# usb-can.net
KiCad netlist of a schematic drawn in EAGLE
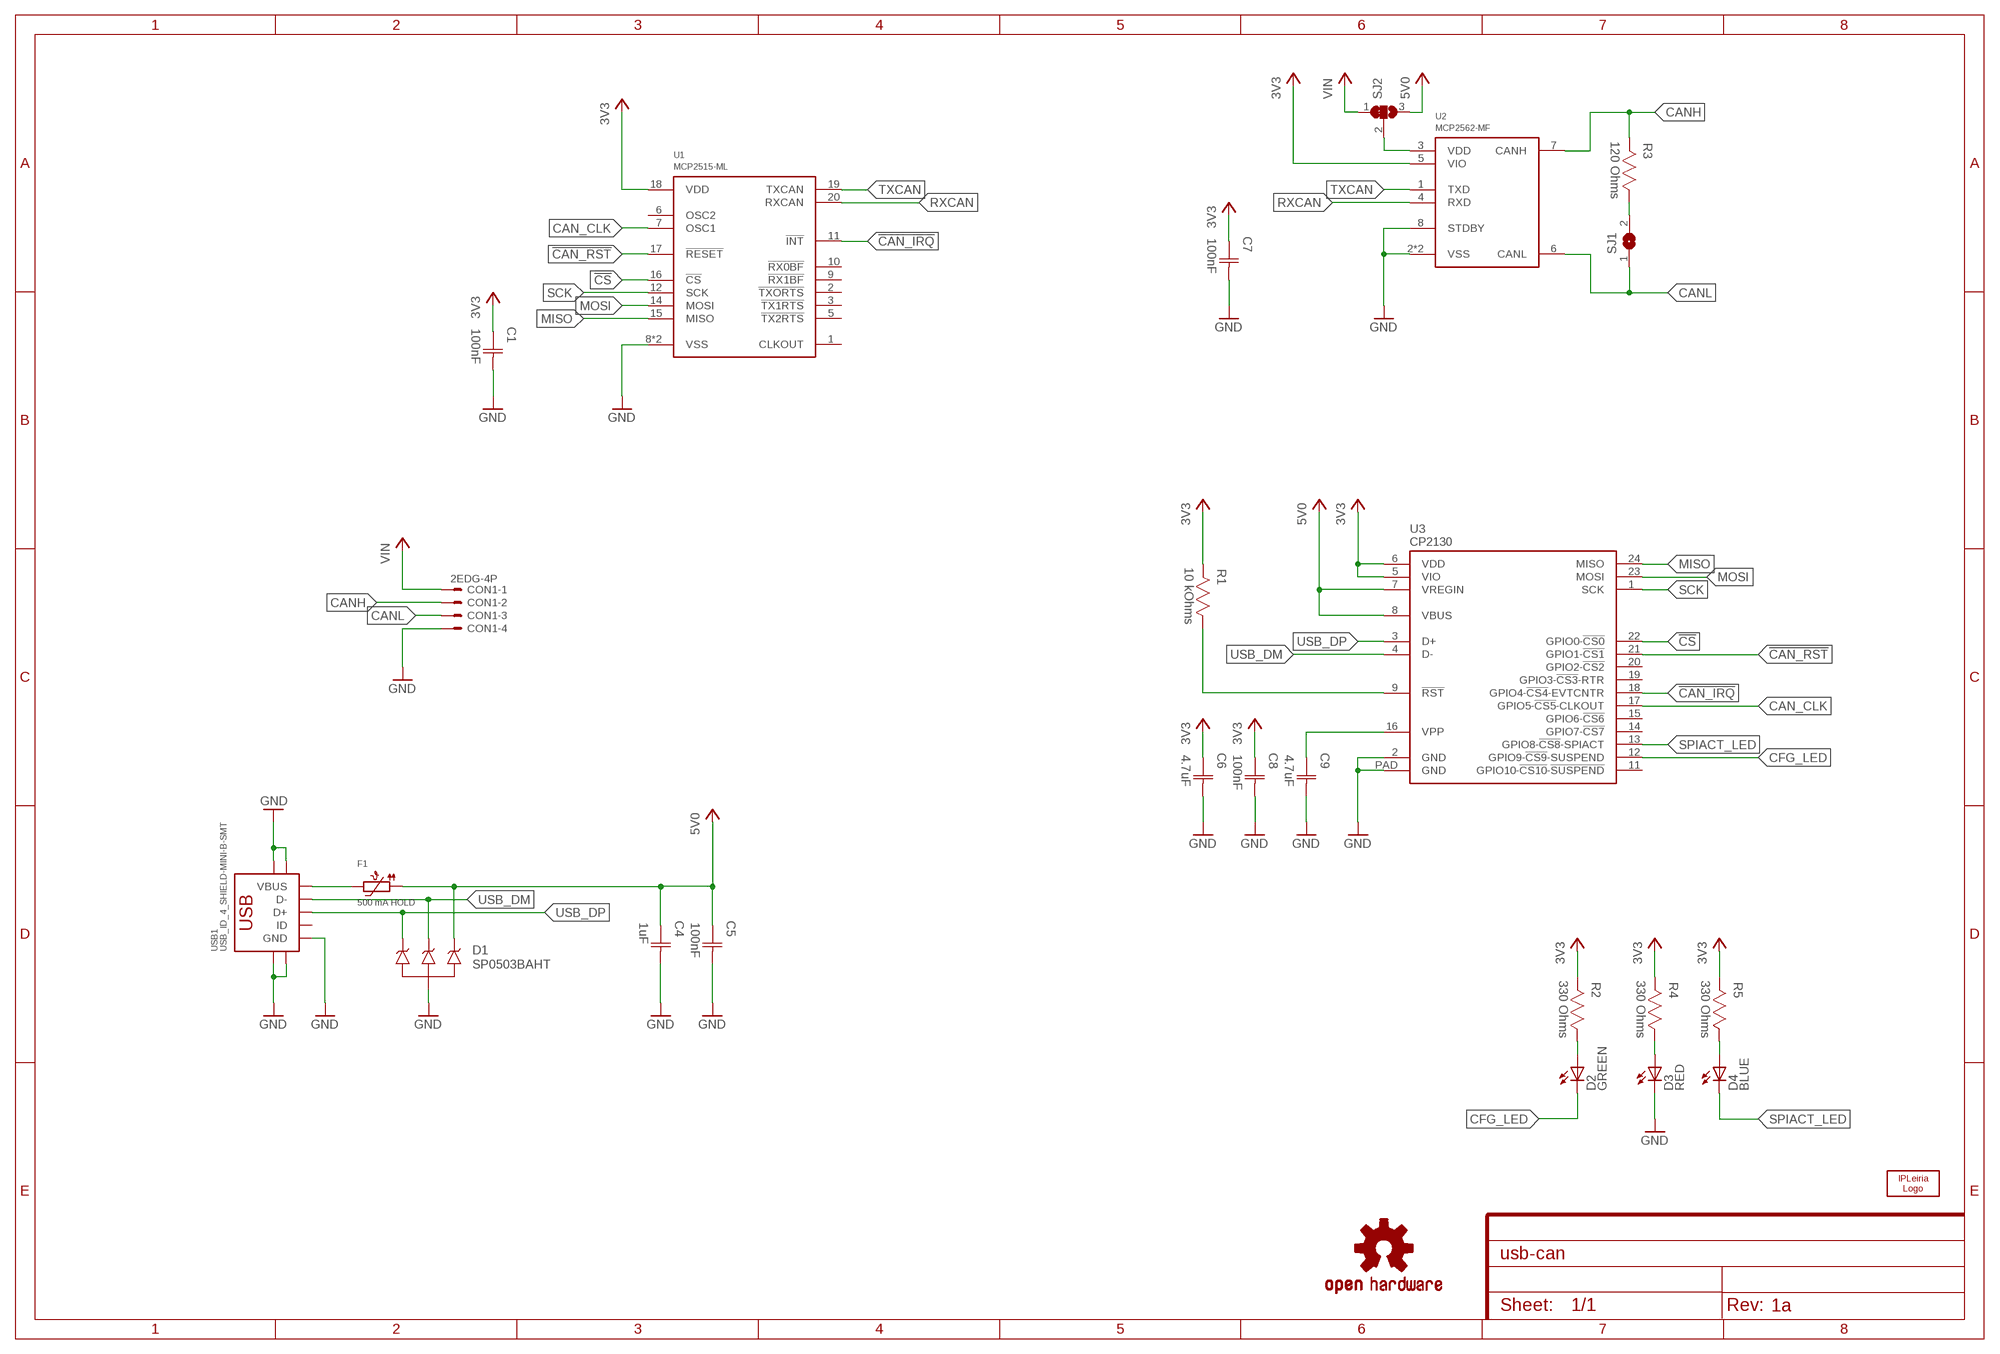
[diagram p0: schematic, sheet 1]

(export (version "E")
  (design (tool "Eeschema 10.0.6"))
  (components
    (comp (ref "C1")
      (value "100nF")
      (footprint "eagle-import:CAP0603")
      (libsource (lib "eagle-import") (part "CAPACITOR-0603"))
    )
    (comp (ref "C4")
      (value "1uF")
      (footprint "eagle-import:CAP0603")
      (libsource (lib "eagle-import") (part "CAPACITOR-0603"))
    )
    (comp (ref "C5")
      (value "100nF")
      (footprint "eagle-import:CAP0603")
      (libsource (lib "eagle-import") (part "CAPACITOR-0603"))
    )
    (comp (ref "C6")
      (value "4.7uF")
      (footprint "eagle-import:CAP0603")
      (libsource (lib "eagle-import") (part "CAPACITOR-0603"))
    )
    (comp (ref "C7")
      (value "100nF")
      (footprint "eagle-import:CAP0603")
      (libsource (lib "eagle-import") (part "CAPACITOR-0603"))
    )
    (comp (ref "C8")
      (value "100nF")
      (footprint "eagle-import:CAP0603")
      (libsource (lib "eagle-import") (part "CAPACITOR-0603"))
    )
    (comp (ref "C9")
      (value "4.7uF")
      (footprint "eagle-import:CAP0603")
      (libsource (lib "eagle-import") (part "CAPACITOR-0603"))
    )
    (comp (ref "CON1")
      (value "2EDG-4P")
      (footprint "eagle-import:2EDG-4P")
      (libsource (lib "eagle-import") (part "2EDG-4P"))
    )
    (comp (ref "D1")
      (value "SP0503BAHT")
      (footprint "eagle-import:SOT143")
      (libsource (lib "eagle-import") (part "SP0503BAHT"))
    )
    (comp (ref "D2")
      (value "GREEN")
      (footprint "eagle-import:0603")
      (libsource (lib "eagle-import") (part "LED0603"))
    )
    (comp (ref "D3")
      (value "RED")
      (footprint "eagle-import:0603")
      (libsource (lib "eagle-import") (part "LED0603"))
    )
    (comp (ref "D4")
      (value "BLUE")
      (footprint "eagle-import:0603")
      (libsource (lib "eagle-import") (part "LED0603"))
    )
    (comp (ref "F1")
      (value "500 mA HOLD")
      (footprint "eagle-import:1206")
      (libsource (lib "eagle-import") (part "PTC1206"))
    )
    (comp (ref "LOGO1")
      (value "IPL-10MM")
      (footprint "eagle-import:IPL_10MM")
      (libsource (lib "eagle-import") (part "IPL-10MM"))
    )
    (comp (ref "LOGO2")
      (value "OSHW-LOGOM")
      (footprint "eagle-import:OSHW-LOGO-M")
      (libsource (lib "eagle-import") (part "OSHW-LOGOM"))
    )
    (comp (ref "R1")
      (value "10 kOhms")
      (footprint "eagle-import:RES0603")
      (libsource (lib "eagle-import") (part "RESISTOR-0603"))
    )
    (comp (ref "R2")
      (value "330 Ohms")
      (footprint "eagle-import:RES0603")
      (libsource (lib "eagle-import") (part "RESISTOR-0603"))
    )
    (comp (ref "R3")
      (value "120 Ohms")
      (footprint "eagle-import:RES0603")
      (libsource (lib "eagle-import") (part "RESISTOR-0603"))
    )
    (comp (ref "R4")
      (value "330 Ohms")
      (footprint "eagle-import:RES0603")
      (libsource (lib "eagle-import") (part "RESISTOR-0603"))
    )
    (comp (ref "R5")
      (value "330 Ohms")
      (footprint "eagle-import:RES0603")
      (libsource (lib "eagle-import") (part "RESISTOR-0603"))
    )
    (comp (ref "SJ1")
      (value "SJS")
      (footprint "eagle-import:SJ_S")
      (libsource (lib "eagle-import") (part "SJS"))
    )
    (comp (ref "SJ2")
      (value "SJ2CS")
      (footprint "eagle-import:SJ2C_S")
      (libsource (lib "eagle-import") (part "SJ2CS"))
    )
    (comp (ref "U1")
      (value "MCP2515-ML")
      (footprint "eagle-import:QFN20")
      (libsource (lib "eagle-import") (part "MCP2515-ML"))
    )
    (comp (ref "U2")
      (value "MCP2562-MF")
      (footprint "eagle-import:DFN8")
      (libsource (lib "eagle-import") (part "MCP2562-MF"))
    )
    (comp (ref "U3")
      (value "CP2130")
      (footprint "eagle-import:QFN24")
      (libsource (lib "eagle-import") (part "CP2130"))
    )
    (comp (ref "USB1")
      (value "USB_ID_4_SHIELD-MINI-B-SMT")
      (footprint "eagle-import:USB-MB-S")
      (libsource (lib "eagle-import") (part "USB_ID_4_SHIELD-MINI-B-SMT"))
    )
  )
  (nets
    (net (code "1") (name "/~{CAN_IRQ}") (class "Default")
      (node (ref "U1") (pin "11") (pinfunction "~{INT}_11") (pintype "bidirectional"))
      (node (ref "U3") (pin "18") (pinfunction "GPIO4-~{CS4}-EVTCNTR_18") (pintype "bidirectional"))
    )
    (net (code "2") (name "/~{CAN_RST}") (class "Default")
      (node (ref "U1") (pin "17") (pinfunction "~{RESET}_17") (pintype "bidirectional"))
      (node (ref "U3") (pin "21") (pinfunction "GPIO1-~{CS1}_21") (pintype "bidirectional"))
    )
    (net (code "3") (name "/~{CS}") (class "Default")
      (node (ref "U1") (pin "16") (pinfunction "~{CS}_16") (pintype "bidirectional"))
      (node (ref "U3") (pin "22") (pinfunction "GPIO0-~{CS0}_22") (pintype "bidirectional"))
    )
    (net (code "4") (name "3V3") (class "Default")
      (node (ref "C1") (pin "1") (pinfunction "C1_1") (pintype "passive"))
      (node (ref "C6") (pin "1") (pinfunction "C1_1") (pintype "passive"))
      (node (ref "C7") (pin "1") (pinfunction "C1_1") (pintype "passive"))
      (node (ref "C8") (pin "1") (pinfunction "C1_1") (pintype "passive"))
      (node (ref "R1") (pin "2") (pinfunction "2_2") (pintype "passive"))
      (node (ref "R2") (pin "2") (pinfunction "2_2") (pintype "passive"))
      (node (ref "R4") (pin "2") (pinfunction "2_2") (pintype "passive"))
      (node (ref "R5") (pin "2") (pinfunction "2_2") (pintype "passive"))
      (node (ref "U1") (pin "18") (pinfunction "VDD_18") (pintype "bidirectional"))
      (node (ref "U2") (pin "5") (pinfunction "VIO_5") (pintype "power_in"))
      (node (ref "U3") (pin "5") (pinfunction "VIO_5") (pintype "bidirectional"))
      (node (ref "U3") (pin "6") (pinfunction "VDD_6") (pintype "bidirectional"))
    )
    (net (code "5") (name "5V0") (class "Default")
      (node (ref "C4") (pin "1") (pinfunction "C1_1") (pintype "passive"))
      (node (ref "C5") (pin "1") (pinfunction "C1_1") (pintype "passive"))
      (node (ref "D1") (pin "4") (pinfunction "4_4") (pintype "bidirectional"))
      (node (ref "F1") (pin "1") (pinfunction "1_1") (pintype "passive"))
      (node (ref "SJ2") (pin "3") (pinfunction "3_3") (pintype "passive"))
      (node (ref "U3") (pin "7") (pinfunction "VREGIN_7") (pintype "bidirectional"))
      (node (ref "U3") (pin "8") (pinfunction "VBUS_8") (pintype "bidirectional"))
    )
    (net (code "6") (name "CANH") (class "Default")
      (node (ref "CON1") (pin "P$2") (pinfunction "S_P$2") (pintype "passive"))
      (node (ref "R3") (pin "2") (pinfunction "2_2") (pintype "passive"))
      (node (ref "U2") (pin "7") (pinfunction "CANH_7") (pintype "bidirectional"))
    )
    (net (code "7") (name "CANL") (class "Default")
      (node (ref "CON1") (pin "P$3") (pinfunction "S_P$3") (pintype "passive"))
      (node (ref "SJ1") (pin "1") (pinfunction "1_1") (pintype "passive"))
      (node (ref "U2") (pin "6") (pinfunction "CANL_6") (pintype "bidirectional"))
    )
    (net (code "8") (name "CAN_CLK") (class "Default")
      (node (ref "U1") (pin "7") (pinfunction "OSC1_7") (pintype "bidirectional"))
      (node (ref "U3") (pin "17") (pinfunction "GPIO5-~{CS5}-CLKOUT_17") (pintype "bidirectional"))
    )
    (net (code "9") (name "CFG_LED") (class "Default")
      (node (ref "D2") (pin "1") (pinfunction "C_1") (pintype "passive"))
      (node (ref "U3") (pin "12") (pinfunction "GPIO9-~{CS9}-SUSPEND_12") (pintype "bidirectional"))
    )
    (net (code "10") (name "GND") (class "Default")
      (node (ref "C1") (pin "2") (pinfunction "C2_2") (pintype "passive"))
      (node (ref "C4") (pin "2") (pinfunction "C2_2") (pintype "passive"))
      (node (ref "C5") (pin "2") (pinfunction "C2_2") (pintype "passive"))
      (node (ref "C6") (pin "2") (pinfunction "C2_2") (pintype "passive"))
      (node (ref "C7") (pin "2") (pinfunction "C2_2") (pintype "passive"))
      (node (ref "C8") (pin "2") (pinfunction "C2_2") (pintype "passive"))
      (node (ref "C9") (pin "2") (pinfunction "C2_2") (pintype "passive"))
      (node (ref "CON1") (pin "P$4") (pinfunction "S_P$4") (pintype "passive"))
      (node (ref "D1") (pin "1") (pinfunction "1_1") (pintype "bidirectional"))
      (node (ref "D3") (pin "1") (pinfunction "C_1") (pintype "passive"))
      (node (ref "U1") (pin "8") (pinfunction "VSS_8") (pintype "bidirectional"))
      (node (ref "U1") (pin "PAD") (pinfunction "VSS_PAD") (pintype "bidirectional"))
      (node (ref "U2") (pin "2") (pinfunction "VSS_2") (pintype "power_in"))
      (node (ref "U2") (pin "8") (pinfunction "STDBY_8") (pintype "bidirectional"))
      (node (ref "U2") (pin "9") (pinfunction "VSS_9") (pintype "power_in"))
      (node (ref "U3") (pin "2") (pinfunction "GND_2") (pintype "bidirectional"))
      (node (ref "U3") (pin "PAD") (pinfunction "GND_PAD") (pintype "bidirectional"))
      (node (ref "USB1") (pin "GND") (pinfunction "GND_GND") (pintype "bidirectional"))
      (node (ref "USB1") (pin "GND1") (pinfunction "SHIELD_GND1") (pintype "bidirectional"))
      (node (ref "USB1") (pin "GND2") (pinfunction "SHIELD_GND2") (pintype "bidirectional"))
      (node (ref "USB1") (pin "GND3") (pinfunction "SHIELD_GND3") (pintype "bidirectional"))
      (node (ref "USB1") (pin "GND4") (pinfunction "SHIELD_GND4") (pintype "bidirectional"))
    )
    (net (code "11") (name "MISO") (class "Default")
      (node (ref "U1") (pin "15") (pinfunction "MISO_15") (pintype "bidirectional"))
      (node (ref "U3") (pin "24") (pinfunction "MISO_24") (pintype "bidirectional"))
    )
    (net (code "12") (name "MOSI") (class "Default")
      (node (ref "U1") (pin "14") (pinfunction "MOSI_14") (pintype "bidirectional"))
      (node (ref "U3") (pin "23") (pinfunction "MOSI_23") (pintype "bidirectional"))
    )
    (net (code "13") (name "Net-(C9-C1)") (class "Default")
      (node (ref "C9") (pin "1") (pinfunction "C1_1") (pintype "passive"))
      (node (ref "U3") (pin "16") (pinfunction "VPP_16") (pintype "bidirectional"))
    )
    (net (code "14") (name "Net-(D2-A)") (class "Default")
      (node (ref "D2") (pin "2") (pinfunction "A_2") (pintype "passive"))
      (node (ref "R2") (pin "1") (pinfunction "1_1") (pintype "passive"))
    )
    (net (code "15") (name "Net-(D3-A)") (class "Default")
      (node (ref "D3") (pin "2") (pinfunction "A_2") (pintype "passive"))
      (node (ref "R4") (pin "1") (pinfunction "1_1") (pintype "passive"))
    )
    (net (code "16") (name "Net-(D4-A)") (class "Default")
      (node (ref "D4") (pin "2") (pinfunction "A_2") (pintype "passive"))
      (node (ref "R5") (pin "1") (pinfunction "1_1") (pintype "passive"))
    )
    (net (code "17") (name "Net-(F1-Pad2)") (class "Default")
      (node (ref "F1") (pin "2") (pinfunction "2_2") (pintype "passive"))
      (node (ref "USB1") (pin "VBUS") (pinfunction "VBUS_VBUS") (pintype "bidirectional"))
    )
    (net (code "18") (name "Net-(R3-Pad1)") (class "Default")
      (node (ref "R3") (pin "1") (pinfunction "1_1") (pintype "passive"))
      (node (ref "SJ1") (pin "2") (pinfunction "2_2") (pintype "passive"))
    )
    (net (code "19") (name "Net-(U2-VDD)") (class "Default")
      (node (ref "SJ2") (pin "2") (pinfunction "2_2") (pintype "passive"))
      (node (ref "U2") (pin "3") (pinfunction "VDD_3") (pintype "power_in"))
    )
    (net (code "20") (name "Net-(U3-~{RST})") (class "Default")
      (node (ref "R1") (pin "1") (pinfunction "1_1") (pintype "passive"))
      (node (ref "U3") (pin "9") (pinfunction "~{RST}_9") (pintype "bidirectional"))
    )
    (net (code "21") (name "RXCAN") (class "Default")
      (node (ref "U1") (pin "20") (pinfunction "RXCAN_20") (pintype "bidirectional"))
      (node (ref "U2") (pin "4") (pinfunction "RXD_4") (pintype "bidirectional"))
    )
    (net (code "22") (name "SCK") (class "Default")
      (node (ref "U1") (pin "12") (pinfunction "SCK_12") (pintype "bidirectional"))
      (node (ref "U3") (pin "1") (pinfunction "SCK_1") (pintype "bidirectional"))
    )
    (net (code "23") (name "SPIACT_LED") (class "Default")
      (node (ref "D4") (pin "1") (pinfunction "C_1") (pintype "passive"))
      (node (ref "U3") (pin "13") (pinfunction "GPIO8-~{CS8}-SPIACT_13") (pintype "bidirectional"))
    )
    (net (code "24") (name "TXCAN") (class "Default")
      (node (ref "U1") (pin "19") (pinfunction "TXCAN_19") (pintype "bidirectional"))
      (node (ref "U2") (pin "1") (pinfunction "TXD_1") (pintype "bidirectional"))
    )
    (net (code "25") (name "USB_DM") (class "Default")
      (node (ref "D1") (pin "3") (pinfunction "3_3") (pintype "bidirectional"))
      (node (ref "U3") (pin "4") (pinfunction "D-_4") (pintype "bidirectional"))
      (node (ref "USB1") (pin "D-") (pinfunction "D-_D-") (pintype "bidirectional"))
    )
    (net (code "26") (name "USB_DP") (class "Default")
      (node (ref "D1") (pin "2") (pinfunction "2_2") (pintype "bidirectional"))
      (node (ref "U3") (pin "3") (pinfunction "D+_3") (pintype "bidirectional"))
      (node (ref "USB1") (pin "D+") (pinfunction "D+_D+") (pintype "bidirectional"))
    )
    (net (code "27") (name "VIN") (class "Default")
      (node (ref "CON1") (pin "P$1") (pinfunction "S_P$1") (pintype "passive"))
      (node (ref "SJ2") (pin "1") (pinfunction "1_1") (pintype "passive"))
    )
    (net (code "28") (name "unconnected-(U1-CLKOUT-Pad1)") (class "Default")
      (node (ref "U1") (pin "1") (pinfunction "CLKOUT_1") (pintype "bidirectional"))
    )
    (net (code "29") (name "unconnected-(U1-OSC2-Pad6)") (class "Default")
      (node (ref "U1") (pin "6") (pinfunction "OSC2_6") (pintype "bidirectional"))
    )
    (net (code "30") (name "unconnected-(U1-~{RX0BF}-Pad10)") (class "Default")
      (node (ref "U1") (pin "10") (pinfunction "~{RX0BF}_10") (pintype "bidirectional"))
    )
    (net (code "31") (name "unconnected-(U1-~{RX1BF}-Pad9)") (class "Default")
      (node (ref "U1") (pin "9") (pinfunction "~{RX1BF}_9") (pintype "bidirectional"))
    )
    (net (code "32") (name "unconnected-(U1-~{TX1RTS}-Pad3)") (class "Default")
      (node (ref "U1") (pin "3") (pinfunction "~{TX1RTS}_3") (pintype "bidirectional"))
    )
    (net (code "33") (name "unconnected-(U1-~{TX2RTS}-Pad5)") (class "Default")
      (node (ref "U1") (pin "5") (pinfunction "~{TX2RTS}_5") (pintype "bidirectional"))
    )
    (net (code "34") (name "unconnected-(U1-~{TXORTS}-Pad2)") (class "Default")
      (node (ref "U1") (pin "2") (pinfunction "~{TXORTS}_2") (pintype "bidirectional"))
    )
    (net (code "35") (name "unconnected-(U3-GPIO2-~{CS2}-Pad20)") (class "Default")
      (node (ref "U3") (pin "20") (pinfunction "GPIO2-~{CS2}_20") (pintype "bidirectional"))
    )
    (net (code "36") (name "unconnected-(U3-GPIO3-~{CS3}-RTR-Pad19)") (class "Default")
      (node (ref "U3") (pin "19") (pinfunction "GPIO3-~{CS3}-RTR_19") (pintype "bidirectional"))
    )
    (net (code "37") (name "unconnected-(U3-GPIO6-~{CS6}-Pad15)") (class "Default")
      (node (ref "U3") (pin "15") (pinfunction "GPIO6-~{CS6}_15") (pintype "bidirectional"))
    )
    (net (code "38") (name "unconnected-(U3-GPIO7-~{CS7}-Pad14)") (class "Default")
      (node (ref "U3") (pin "14") (pinfunction "GPIO7-~{CS7}_14") (pintype "bidirectional"))
    )
    (net (code "39") (name "unconnected-(U3-GPIO10-~{CS10}-~{SUSPEND}-Pad11)") (class "Default")
      (node (ref "U3") (pin "11") (pinfunction "GPIO10-~{CS10}-~{SUSPEND}_11") (pintype "bidirectional"))
    )
    (net (code "40") (name "unconnected-(USB1-PadID)") (class "Default")
      (node (ref "USB1") (pin "ID") (pinfunction "ID_ID") (pintype "bidirectional"))
    )
  )
)
